# IRsch.net
KiCad netlist of a schematic drawn in Altium Designer
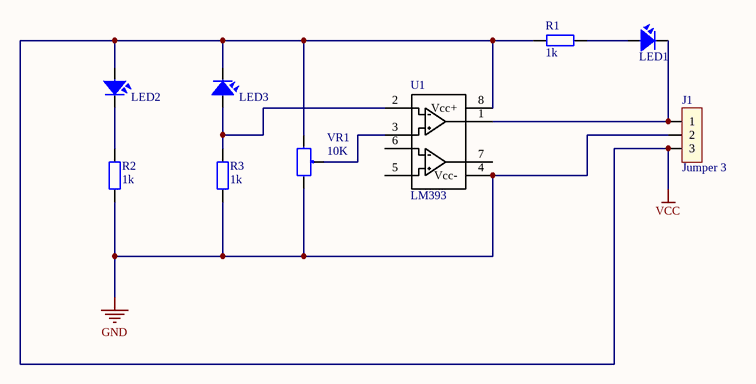
[diagram p0: IRsch.SchDoc]

(export (version "E")
  (design (tool "Eeschema 10.0.6"))
  (components
    (comp (ref "J1") (value "Jumper 3") (footprint "JP3H") (libsource (lib "My Library") (part "JP3")))
    (comp (ref "LED1")
      (value "LED")
      (footprint "LED-3")
      (description "LED Single colour Green and Red")
      (libsource (lib "syhaunguyen") (part "LED"))
    )
    (comp (ref "LED2")
      (value "LED")
      (footprint "LED-5-WHITE")
      (description "LED Single colour Green and Red")
      (libsource (lib "syhaunguyen") (part "LED"))
    )
    (comp (ref "LED3")
      (value "LED")
      (footprint "LED-5-WHITE")
      (description "LED Single colour Green and Red")
      (libsource (lib "syhaunguyen") (part "LED"))
    )
    (comp (ref "R1")
      (value "1k")
      (footprint "R1/2W")
      (description "Resistor 1/4W")
      (libsource (lib "syhaunguyen") (part "R1/4W"))
    )
    (comp (ref "R2")
      (value "1k")
      (footprint "R1/2W")
      (description "Resistor 1/4W")
      (libsource (lib "syhaunguyen") (part "R1/4W"))
    )
    (comp (ref "R3")
      (value "1k")
      (footprint "R1/2W")
      (description "Resistor 1/4W")
      (libsource (lib "syhaunguyen") (part "R1/4W"))
    )
    (comp (ref "U1")
      (value "LM393")
      (footprint "DIP8")
      (description "IC DUAL COMPARATOR")
      (libsource (lib "LIBRARY") (part "LM393"))
    )
    (comp (ref "VR1")
      (value "10K")
      (footprint "VR")
      (description "Var Resistor")
      (libsource (lib "syhaunguyen") (part "VR"))
    )
  )
  (nets
    (net (code "1") (name "GND") (class "Default")
      (node (ref "J1") (pin "2") (pinfunction "2_2") (pintype "passive"))
      (node (ref "R2") (pin "1") (pinfunction "1_1") (pintype "passive"))
      (node (ref "R3") (pin "1") (pinfunction "1_1") (pintype "passive"))
      (node (ref "U1") (pin "4") (pinfunction "Vcc-_4") (pintype "passive"))
      (node (ref "VR1") (pin "3") (pinfunction "3_3") (pintype "passive"))
    )
    (net (code "2") (name "Net-(J1-Pad1)") (class "Default")
      (node (ref "J1") (pin "1") (pinfunction "1_1") (pintype "passive"))
      (node (ref "LED1") (pin "2") (pinfunction "2_2") (pintype "passive"))
      (node (ref "U1") (pin "1") (pintype "passive"))
    )
    (net (code "3") (name "Net-(LED1-Pad1)") (class "Default")
      (node (ref "LED1") (pin "1") (pinfunction "1_1") (pintype "passive"))
      (node (ref "R1") (pin "2") (pinfunction "2_2") (pintype "passive"))
    )
    (net (code "4") (name "Net-(LED2-Pad2)") (class "Default")
      (node (ref "LED2") (pin "2") (pinfunction "2_2") (pintype "passive"))
      (node (ref "R2") (pin "2") (pinfunction "2_2") (pintype "passive"))
    )
    (net (code "5") (name "Net-(LED3-Pad1)") (class "Default")
      (node (ref "LED3") (pin "1") (pinfunction "1_1") (pintype "passive"))
      (node (ref "R3") (pin "2") (pinfunction "2_2") (pintype "passive"))
      (node (ref "U1") (pin "2") (pintype "passive"))
    )
    (net (code "6") (name "Net-(U1-Pad3)") (class "Default")
      (node (ref "U1") (pin "3") (pintype "passive"))
      (node (ref "VR1") (pin "2") (pinfunction "2_2") (pintype "passive"))
    )
    (net (code "7") (name "VCC") (class "Default")
      (node (ref "J1") (pin "3") (pinfunction "3_3") (pintype "passive"))
      (node (ref "LED2") (pin "1") (pinfunction "1_1") (pintype "passive"))
      (node (ref "LED3") (pin "2") (pinfunction "2_2") (pintype "passive"))
      (node (ref "R1") (pin "1") (pinfunction "1_1") (pintype "passive"))
      (node (ref "U1") (pin "8") (pinfunction "Vcc+_8") (pintype "passive"))
      (node (ref "VR1") (pin "1") (pinfunction "1_1") (pintype "passive"))
    )
    (net (code "8") (name "unconnected-(U1-Pad5)") (class "Default")
      (node (ref "U1") (pin "5") (pintype "passive"))
    )
    (net (code "9") (name "unconnected-(U1-Pad6)") (class "Default")
      (node (ref "U1") (pin "6") (pintype "passive"))
    )
    (net (code "10") (name "unconnected-(U1-Pad7)") (class "Default")
      (node (ref "U1") (pin "7") (pintype "passive"))
    )
  )
)
